# K6.net
KiCad netlist of a schematic drawn in Altium Designer
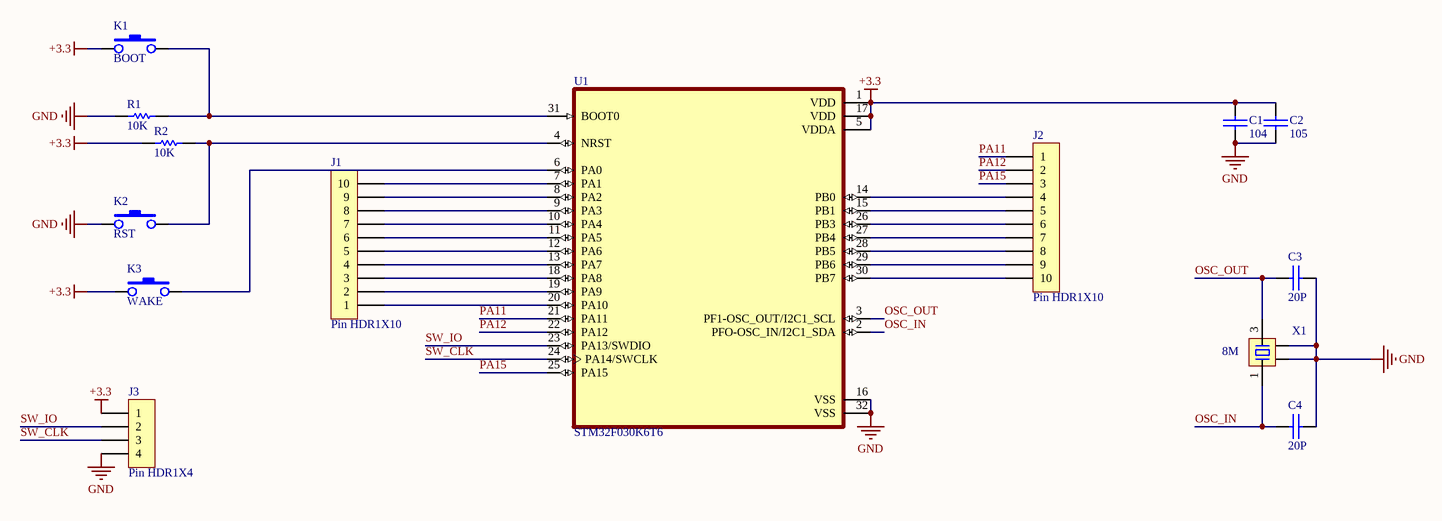
[diagram p0: K6.SchDoc]

(export (version "E")
  (design (tool "Eeschema 10.0.6"))
  (components
    (comp (ref "C1")
      (value "104")
      (footprint "0805C")
      (description "无极性电容")
      (libsource (lib "常用元件-电容") (part "CAP"))
    )
    (comp (ref "C2")
      (value "105")
      (footprint "0805C")
      (description "无极性电容")
      (libsource (lib "常用元件-电容") (part "CAP"))
    )
    (comp (ref "C3")
      (value "20P")
      (footprint "0805C")
      (description "无极性电容")
      (libsource (lib "常用元件-电容") (part "CAP"))
    )
    (comp (ref "C4")
      (value "20P")
      (footprint "0805C")
      (description "无极性电容")
      (libsource (lib "常用元件-电容") (part "CAP"))
    )
    (comp (ref "J1")
      (value "Pin HDR1X10")
      (footprint "Pin HDR1X10/2.54mm-S")
      (libsource (lib "") (part "Pin HDR1X10_1"))
    )
    (comp (ref "J2")
      (value "Pin HDR1X10")
      (footprint "Pin HDR1X10/2.54mm-S")
      (libsource (lib "常用元件-排针") (part "Pin HDR1X10"))
    )
    (comp (ref "J3")
      (value "Pin HDR1X4")
      (footprint "Pin HDR1X4/2.54mm-S")
      (libsource (lib "常用元件-排针") (part "Pin HDR1X4"))
    )
    (comp (ref "K1")
      (value "BOOT")
      (footprint "SW-SMD_L3.9-W2.9-P4.15-LS5.0")
      (libsource (lib "开关-轻触开关") (part "KEY"))
    )
    (comp (ref "K2")
      (value "RST")
      (footprint "SW-SMD_L3.9-W2.9-P4.15-LS5.0")
      (libsource (lib "开关-轻触开关") (part "KEY"))
    )
    (comp (ref "K3")
      (value "WAKE")
      (footprint "SW-SMD_L3.9-W2.9-P4.15-LS5.0")
      (libsource (lib "开关-轻触开关") (part "KEY"))
    )
    (comp (ref "R1") (value "10K") (footprint "0805R") (libsource (lib "常用元件-电阻") (part "RES")))
    (comp (ref "R2") (value "10K") (footprint "0805R") (libsource (lib "常用元件-电阻") (part "RES")))
    (comp (ref "U1")
      (value "STM32F030K6T6")
      (footprint "LQFP32 7X7")
      (fields (field (name "MF") "{'manufacturer': u'STMicroelectronics'}"))
      (libsource (lib "*") (part "STM32F030K6T6"))
    )
    (comp (ref "X1")
      (value "8M")
      (footprint "OSC 5032-4P")
      (description "4脚无源晶振")
      (libsource (lib "常用元件-晶振") (part "XTAL-4P"))
    )
  )
  (nets
    (net (code "1") (name "+3.3") (class "Default")
      (node (ref "C1") (pin "2") (pinfunction "2_2") (pintype "passive"))
      (node (ref "C2") (pin "2") (pinfunction "2_2") (pintype "passive"))
      (node (ref "J3") (pin "1") (pinfunction "1_1") (pintype "passive"))
      (node (ref "K1") (pin "1") (pinfunction "1_1") (pintype "passive"))
      (node (ref "K3") (pin "1") (pinfunction "1_1") (pintype "passive"))
      (node (ref "R2") (pin "1") (pinfunction "1_1") (pintype "passive"))
      (node (ref "U1") (pin "1") (pinfunction "VDD_1") (pintype "power_in"))
      (node (ref "U1") (pin "17") (pinfunction "VDD_17") (pintype "power_in"))
      (node (ref "U1") (pin "5") (pinfunction "VDDA_5") (pintype "power_in"))
    )
    (net (code "2") (name "/OSC_IN") (class "Default")
      (node (ref "C4") (pin "1") (pinfunction "1_1") (pintype "passive"))
      (node (ref "U1") (pin "2") (pinfunction "PFO-OSC_IN/I2C1_SDA_2") (pintype "bidirectional"))
      (node (ref "X1") (pin "1") (pinfunction "1_1") (pintype "passive"))
    )
    (net (code "3") (name "/OSC_OUT") (class "Default")
      (node (ref "C3") (pin "1") (pinfunction "1_1") (pintype "passive"))
      (node (ref "U1") (pin "3") (pinfunction "PF1-OSC_OUT/I2C1_SCL_3") (pintype "bidirectional"))
      (node (ref "X1") (pin "3") (pinfunction "3_3") (pintype "passive"))
    )
    (net (code "4") (name "/PA11") (class "Default")
      (node (ref "J2") (pin "1") (pinfunction "1_1") (pintype "passive"))
      (node (ref "U1") (pin "21") (pinfunction "PA11_21") (pintype "bidirectional"))
    )
    (net (code "5") (name "/PA12") (class "Default")
      (node (ref "J2") (pin "2") (pinfunction "2_2") (pintype "passive"))
      (node (ref "U1") (pin "22") (pinfunction "PA12_22") (pintype "bidirectional"))
    )
    (net (code "6") (name "/PA15") (class "Default")
      (node (ref "J2") (pin "3") (pinfunction "3_3") (pintype "passive"))
      (node (ref "U1") (pin "25") (pinfunction "PA15_25") (pintype "bidirectional"))
    )
    (net (code "7") (name "/SW_CLK") (class "Default")
      (node (ref "J3") (pin "3") (pinfunction "3_3") (pintype "passive"))
      (node (ref "U1") (pin "24") (pinfunction "PA14/SWCLK_24") (pintype "bidirectional"))
    )
    (net (code "8") (name "/SW_IO") (class "Default")
      (node (ref "J3") (pin "2") (pinfunction "2_2") (pintype "passive"))
      (node (ref "U1") (pin "23") (pinfunction "PA13/SWDIO_23") (pintype "bidirectional"))
    )
    (net (code "9") (name "GND") (class "Default")
      (node (ref "C1") (pin "1") (pinfunction "1_1") (pintype "passive"))
      (node (ref "C2") (pin "1") (pinfunction "1_1") (pintype "passive"))
      (node (ref "C3") (pin "2") (pinfunction "2_2") (pintype "passive"))
      (node (ref "C4") (pin "2") (pinfunction "2_2") (pintype "passive"))
      (node (ref "J3") (pin "4") (pinfunction "4_4") (pintype "passive"))
      (node (ref "K2") (pin "1") (pinfunction "1_1") (pintype "passive"))
      (node (ref "R1") (pin "1") (pinfunction "1_1") (pintype "passive"))
      (node (ref "U1") (pin "16") (pinfunction "VSS_16") (pintype "power_in"))
      (node (ref "U1") (pin "32") (pinfunction "VSS_32") (pintype "power_in"))
      (node (ref "X1") (pin "2") (pinfunction "2_2") (pintype "passive"))
      (node (ref "X1") (pin "4") (pinfunction "4_4") (pintype "passive"))
    )
    (net (code "10") (name "Net-(U1-BOOT0)") (class "Default")
      (node (ref "K1") (pin "3") (pinfunction "3_3") (pintype "passive"))
      (node (ref "R1") (pin "2") (pinfunction "2_2") (pintype "passive"))
      (node (ref "U1") (pin "31") (pinfunction "BOOT0_31") (pintype "input"))
    )
    (net (code "11") (name "Net-(U1-NRST)") (class "Default")
      (node (ref "K2") (pin "3") (pinfunction "3_3") (pintype "passive"))
      (node (ref "R2") (pin "2") (pinfunction "2_2") (pintype "passive"))
      (node (ref "U1") (pin "4") (pinfunction "NRST_4") (pintype "bidirectional"))
    )
    (net (code "12") (name "Net-(U1-PA0)") (class "Default")
      (node (ref "K3") (pin "3") (pinfunction "3_3") (pintype "passive"))
      (node (ref "U1") (pin "6") (pinfunction "PA0_6") (pintype "bidirectional"))
    )
    (net (code "13") (name "Net-(U1-PA1)") (class "Default")
      (node (ref "J1") (pin "10") (pinfunction "10_10") (pintype "passive"))
      (node (ref "U1") (pin "7") (pinfunction "PA1_7") (pintype "bidirectional"))
    )
    (net (code "14") (name "Net-(U1-PA2)") (class "Default")
      (node (ref "J1") (pin "9") (pinfunction "9_9") (pintype "passive"))
      (node (ref "U1") (pin "8") (pinfunction "PA2_8") (pintype "bidirectional"))
    )
    (net (code "15") (name "Net-(U1-PA3)") (class "Default")
      (node (ref "J1") (pin "8") (pinfunction "8_8") (pintype "passive"))
      (node (ref "U1") (pin "9") (pinfunction "PA3_9") (pintype "bidirectional"))
    )
    (net (code "16") (name "Net-(U1-PA4)") (class "Default")
      (node (ref "J1") (pin "7") (pinfunction "7_7") (pintype "passive"))
      (node (ref "U1") (pin "10") (pinfunction "PA4_10") (pintype "bidirectional"))
    )
    (net (code "17") (name "Net-(U1-PA5)") (class "Default")
      (node (ref "J1") (pin "6") (pinfunction "6_6") (pintype "passive"))
      (node (ref "U1") (pin "11") (pinfunction "PA5_11") (pintype "bidirectional"))
    )
    (net (code "18") (name "Net-(U1-PA6)") (class "Default")
      (node (ref "J1") (pin "5") (pinfunction "5_5") (pintype "passive"))
      (node (ref "U1") (pin "12") (pinfunction "PA6_12") (pintype "bidirectional"))
    )
    (net (code "19") (name "Net-(U1-PA7)") (class "Default")
      (node (ref "J1") (pin "4") (pinfunction "4_4") (pintype "passive"))
      (node (ref "U1") (pin "13") (pinfunction "PA7_13") (pintype "bidirectional"))
    )
    (net (code "20") (name "Net-(U1-PA8)") (class "Default")
      (node (ref "J1") (pin "3") (pinfunction "3_3") (pintype "passive"))
      (node (ref "U1") (pin "18") (pinfunction "PA8_18") (pintype "bidirectional"))
    )
    (net (code "21") (name "Net-(U1-PA9)") (class "Default")
      (node (ref "J1") (pin "2") (pinfunction "2_2") (pintype "passive"))
      (node (ref "U1") (pin "19") (pinfunction "PA9_19") (pintype "bidirectional"))
    )
    (net (code "22") (name "Net-(U1-PA10)") (class "Default")
      (node (ref "J1") (pin "1") (pinfunction "1_1") (pintype "passive"))
      (node (ref "U1") (pin "20") (pinfunction "PA10_20") (pintype "bidirectional"))
    )
    (net (code "23") (name "Net-(U1-PB0)") (class "Default")
      (node (ref "J2") (pin "4") (pinfunction "4_4") (pintype "passive"))
      (node (ref "U1") (pin "14") (pinfunction "PB0_14") (pintype "bidirectional"))
    )
    (net (code "24") (name "Net-(U1-PB1)") (class "Default")
      (node (ref "J2") (pin "5") (pinfunction "5_5") (pintype "passive"))
      (node (ref "U1") (pin "15") (pinfunction "PB1_15") (pintype "bidirectional"))
    )
    (net (code "25") (name "Net-(U1-PB3)") (class "Default")
      (node (ref "J2") (pin "6") (pinfunction "6_6") (pintype "passive"))
      (node (ref "U1") (pin "26") (pinfunction "PB3_26") (pintype "bidirectional"))
    )
    (net (code "26") (name "Net-(U1-PB4)") (class "Default")
      (node (ref "J2") (pin "7") (pinfunction "7_7") (pintype "passive"))
      (node (ref "U1") (pin "27") (pinfunction "PB4_27") (pintype "bidirectional"))
    )
    (net (code "27") (name "Net-(U1-PB5)") (class "Default")
      (node (ref "J2") (pin "8") (pinfunction "8_8") (pintype "passive"))
      (node (ref "U1") (pin "28") (pinfunction "PB5_28") (pintype "bidirectional"))
    )
    (net (code "28") (name "Net-(U1-PB6)") (class "Default")
      (node (ref "J2") (pin "9") (pinfunction "9_9") (pintype "passive"))
      (node (ref "U1") (pin "29") (pinfunction "PB6_29") (pintype "bidirectional"))
    )
    (net (code "29") (name "Net-(U1-PB7)") (class "Default")
      (node (ref "J2") (pin "10") (pinfunction "10_10") (pintype "passive"))
      (node (ref "U1") (pin "30") (pinfunction "PB7_30") (pintype "bidirectional"))
    )
  )
)
